# Power.net
KiCad netlist of a schematic drawn in Altium Designer
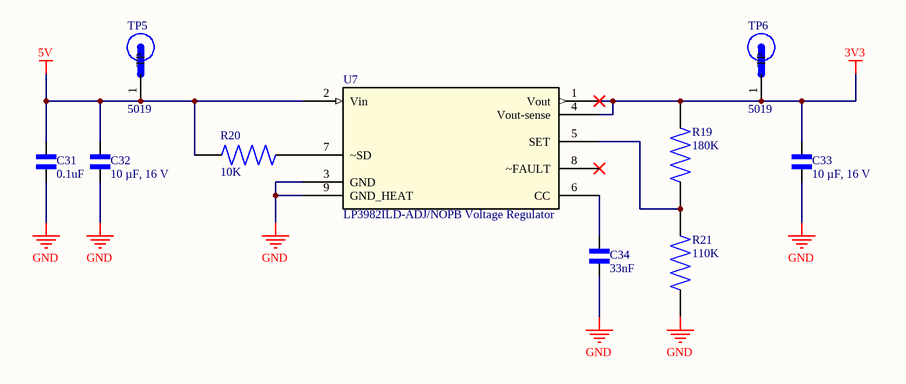
[diagram p0: Power.SchDoc]

(export (version "E")
  (design (tool "Eeschema 10.0.6"))
  (components
    (comp (ref "C31")
      (value "0.1uF")
      (footprint "C0402")
      (description "CAP CER 0.1UF 6.3V X5R 01005")
      (fields
        (field (name "MANUFACTURER") "Murata")
        (field (name "MANUFACTURER PART NUMBER") "GRM022R60J104KE15L")
      )
      (libsource (lib "nnts") (part "GRM022R60J104KE15L"))
    )
    (comp (ref "C32")
      (value "10 µF, 16 V")
      (footprint "C0805")
      (fields
        (field (name "MANUFACTURER") "TDK")
        (field (name "MANUFACTURER PART NUMBER") "C2012X5R1C106K085AC")
        (field (name "TOLERANCE") "10%")
      )
      (libsource (lib "nnts") (part "C2012X5R1C106K085AC"))
    )
    (comp (ref "C33")
      (value "10 µF, 16 V")
      (footprint "C0805")
      (fields
        (field (name "MANUFACTURER") "TDK")
        (field (name "MANUFACTURER PART NUMBER") "C2012X5R1C106K085AC")
        (field (name "TOLERANCE") "10%")
      )
      (libsource (lib "nnts") (part "C2012X5R1C106K085AC"))
    )
    (comp (ref "C34")
      (value "33nF")
      (footprint "C0402")
      (description "Multilayer Ceramic Capacitors MLCC - SMD/SMT 6.3V 0.033uF X5R 01005 10%")
      (fields
        (field (name "MANUFACTURER") "Kyocera AVX")
        (field (name "MANUFACTURER PART NUMBER") "CM02X5R333K06AH")
      )
      (libsource (lib "nnts") (part "CM02X5R333K06AH"))
    )
    (comp (ref "R19")
      (value "180K")
      (footprint "R0603 Vishay")
      (fields
        (field (name "MANUFACTURER") "Vishay")
        (field (name "MANUFACTURER PART NUMBER") "CRCW0201180KFNED")
        (field (name "TOLERANCE") "1%")
      )
      (libsource (lib "nnts") (part "CRCW0201180KFNED"))
    )
    (comp (ref "R20")
      (value "10K")
      (footprint "R0603 Vishay")
      (fields
        (field (name "MANUFACTURER") "Vishay")
        (field (name "MANUFACTURER PART NUMBER") "CRCW020110K0FNED")
        (field (name "TOLERANCE") "1%")
      )
      (libsource (lib "nnts") (part "CRCW020110K0FNED"))
    )
    (comp (ref "R21")
      (value "110K")
      (footprint "R0603 Vishay")
      (description "RES SMD 110K OHM 1% 1/20W 0201")
      (fields
        (field (name "MANUFACTURER") "Vishay")
        (field (name "MANUFACTURER PART NUMBER") "CRCW0201110KFNED")
      )
      (libsource (lib "nnts") (part "CRCW0201110KFNED"))
    )
    (comp (ref "TP5")
      (value "5019")
      (footprint "TP380X203")
      (description "PC Test Point, Miniature Phosphor Bronze, Silver Plating Surface Mount Mounting Type")
      (fields (field (name "MF") "Keystone Electronics") (field (name "DIGI-KEY_PART_NUMBER") "36-5019CT-ND"))
      (libsource (lib "nnts") (part "5019"))
    )
    (comp (ref "TP6")
      (value "5019")
      (footprint "TP380X203")
      (description "PC Test Point, Miniature Phosphor Bronze, Silver Plating Surface Mount Mounting Type")
      (fields (field (name "MF") "Keystone Electronics") (field (name "DIGI-KEY_PART_NUMBER") "36-5019CT-ND"))
      (libsource (lib "nnts") (part "5019"))
    )
    (comp (ref "U7")
      (value "LP3982ILD-ADJ/NOPB Voltage Regulator")
      (footprint "LP3982ILD-ADJ")
      (description "https://www.ti.com/product/LP3982?HQS=TI-null-null-octopart-df-pf-null-wwe")
      (fields
        (field (name "MANUFACTURER_PART_NUMBER") "LP3982ILD-ADJ/NOPB")
        (field (name "COPYRIGHT") "Copyright (C) 2018 Accelerated Designs. All rights reserved")
      )
      (libsource (lib "nnts") (part "LP3982ILD-ADJ"))
    )
  )
  (nets
    (net (code "1") (name "3V3") (class "Default")
      (node (ref "C33") (pin "2") (pinfunction "2_2") (pintype "passive"))
      (node (ref "R19") (pin "2") (pinfunction "2_2") (pintype "passive"))
      (node (ref "TP6") (pin "1") (pinfunction "TP_1") (pintype "passive"))
      (node (ref "U7") (pin "1") (pinfunction "Vout_1") (pintype "output"))
      (node (ref "U7") (pin "4") (pinfunction "Vout-sense_4") (pintype "passive"))
    )
    (net (code "2") (name "5V") (class "Default")
      (node (ref "C31") (pin "2") (pinfunction "2_2") (pintype "passive"))
      (node (ref "C32") (pin "2") (pinfunction "2_2") (pintype "passive"))
      (node (ref "R20") (pin "1") (pinfunction "1_1") (pintype "passive"))
      (node (ref "TP5") (pin "1") (pinfunction "TP_1") (pintype "passive"))
      (node (ref "U7") (pin "2") (pinfunction "Vin_2") (pintype "input"))
    )
    (net (code "3") (name "GND") (class "Default")
      (node (ref "C31") (pin "1") (pinfunction "1_1") (pintype "passive"))
      (node (ref "C32") (pin "1") (pinfunction "1_1") (pintype "passive"))
      (node (ref "C33") (pin "1") (pinfunction "1_1") (pintype "passive"))
      (node (ref "C34") (pin "1") (pinfunction "1_1") (pintype "passive"))
      (node (ref "R21") (pin "1") (pinfunction "1_1") (pintype "passive"))
      (node (ref "U7") (pin "3") (pinfunction "GND_3") (pintype "passive"))
      (node (ref "U7") (pin "9") (pinfunction "GND_HEAT_9") (pintype "passive"))
    )
    (net (code "4") (name "Net-(U7-CC)") (class "Default")
      (node (ref "C34") (pin "2") (pinfunction "2_2") (pintype "passive"))
      (node (ref "U7") (pin "6") (pinfunction "CC_6") (pintype "passive"))
    )
    (net (code "5") (name "Net-(U7-SET)") (class "Default")
      (node (ref "R19") (pin "1") (pinfunction "1_1") (pintype "passive"))
      (node (ref "R21") (pin "2") (pinfunction "2_2") (pintype "passive"))
      (node (ref "U7") (pin "5") (pinfunction "SET_5") (pintype "passive"))
    )
    (net (code "6") (name "Net-(U7-~SD)") (class "Default")
      (node (ref "R20") (pin "2") (pinfunction "2_2") (pintype "passive"))
      (node (ref "U7") (pin "7") (pinfunction "~SD_7") (pintype "passive"))
    )
    (net (code "7") (name "unconnected-(U7-~FAULT-Pad8)") (class "Default")
      (node (ref "U7") (pin "8") (pinfunction "~FAULT_8") (pintype "passive+no_connect"))
    )
  )
)
